# untitled.net
KiCad netlist of a schematic drawn in EAGLE
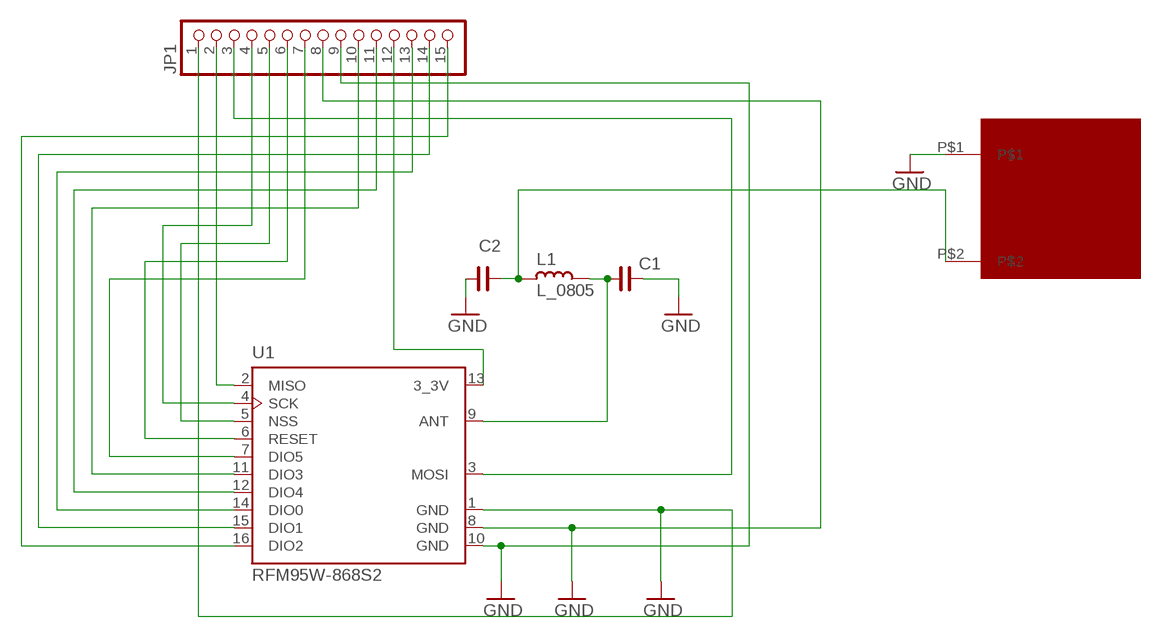
[diagram p0: schematic, sheet 1]

(export (version "E")
  (design (tool "Eeschema 10.0.6"))
  (components
    (comp (ref "C1")
      (value "C_0805")
      (footprint "eagle-import:C0805")
      (libsource (lib "eagle-import") (part "C_0805"))
    )
    (comp (ref "C2")
      (value "C_0805")
      (footprint "eagle-import:C0805")
      (libsource (lib "eagle-import") (part "C_0805"))
    )
    (comp (ref "JP1")
      (value "PINHD-1X15")
      (footprint "eagle-import:1X15")
      (libsource (lib "eagle-import") (part "PINHD-1X15"))
    )
    (comp (ref "L1")
      (value "L_0805")
      (footprint "eagle-import:L0805")
      (libsource (lib "eagle-import") (part "L_0805"))
    )
    (comp (ref "U$1")
      (value "868")
      (footprint "eagle-import:868")
      (libsource (lib "eagle-import") (part "868"))
    )
    (comp (ref "U1")
      (value "RFM95W-868S2")
      (footprint "eagle-import:XCVR_RFM95W-868S2")
      (fields (field (name "MF") "RF"))
      (libsource (lib "eagle-import") (part "RFM95W-868S2"))
    )
  )
  (nets
    (net (code "1") (name "GND") (class "Default")
      (node (ref "C1") (pin "2") (pinfunction "2_2") (pintype "passive"))
      (node (ref "C2") (pin "1") (pinfunction "1_1") (pintype "passive"))
      (node (ref "JP1") (pin "1") (pinfunction "1_1") (pintype "passive"))
      (node (ref "JP1") (pin "8") (pinfunction "8_8") (pintype "passive"))
      (node (ref "JP1") (pin "9") (pinfunction "9_9") (pintype "passive"))
      (node (ref "U$1") (pin "P$1") (pinfunction "P$1_P$1") (pintype "bidirectional"))
      (node (ref "U1") (pin "1") (pinfunction "GND_1") (pintype "power_in"))
      (node (ref "U1") (pin "10") (pinfunction "GND_10") (pintype "power_in"))
      (node (ref "U1") (pin "8") (pinfunction "GND_8") (pintype "power_in"))
    )
    (net (code "2") (name "Net-(C2-Pad2)") (class "Default")
      (node (ref "C2") (pin "2") (pinfunction "2_2") (pintype "passive"))
      (node (ref "L1") (pin "2") (pinfunction "2_2") (pintype "passive"))
      (node (ref "U$1") (pin "P$2") (pinfunction "P$2_P$2") (pintype "bidirectional"))
    )
    (net (code "3") (name "Net-(U1-3_3V)") (class "Default")
      (node (ref "JP1") (pin "12") (pinfunction "12_12") (pintype "passive"))
      (node (ref "U1") (pin "13") (pinfunction "3_3V_13") (pintype "power_in"))
    )
    (net (code "4") (name "Net-(U1-ANT)") (class "Default")
      (node (ref "C1") (pin "1") (pinfunction "1_1") (pintype "passive"))
      (node (ref "L1") (pin "1") (pinfunction "1_1") (pintype "passive"))
      (node (ref "U1") (pin "9") (pinfunction "ANT_9") (pintype "passive"))
    )
    (net (code "5") (name "Net-(U1-DIO0)") (class "Default")
      (node (ref "JP1") (pin "13") (pinfunction "13_13") (pintype "passive"))
      (node (ref "U1") (pin "14") (pinfunction "DIO0_14") (pintype "bidirectional"))
    )
    (net (code "6") (name "Net-(U1-DIO1)") (class "Default")
      (node (ref "JP1") (pin "14") (pinfunction "14_14") (pintype "passive"))
      (node (ref "U1") (pin "15") (pinfunction "DIO1_15") (pintype "bidirectional"))
    )
    (net (code "7") (name "Net-(U1-DIO2)") (class "Default")
      (node (ref "JP1") (pin "15") (pinfunction "15_15") (pintype "passive"))
      (node (ref "U1") (pin "16") (pinfunction "DIO2_16") (pintype "bidirectional"))
    )
    (net (code "8") (name "Net-(U1-DIO3)") (class "Default")
      (node (ref "JP1") (pin "10") (pinfunction "10_10") (pintype "passive"))
      (node (ref "U1") (pin "11") (pinfunction "DIO3_11") (pintype "bidirectional"))
    )
    (net (code "9") (name "Net-(U1-DIO4)") (class "Default")
      (node (ref "JP1") (pin "11") (pinfunction "11_11") (pintype "passive"))
      (node (ref "U1") (pin "12") (pinfunction "DIO4_12") (pintype "bidirectional"))
    )
    (net (code "10") (name "Net-(U1-DIO5)") (class "Default")
      (node (ref "JP1") (pin "7") (pinfunction "7_7") (pintype "passive"))
      (node (ref "U1") (pin "7") (pinfunction "DIO5_7") (pintype "bidirectional"))
    )
    (net (code "11") (name "Net-(U1-MISO)") (class "Default")
      (node (ref "JP1") (pin "2") (pinfunction "2_2") (pintype "passive"))
      (node (ref "U1") (pin "2") (pinfunction "MISO_2") (pintype "input"))
    )
    (net (code "12") (name "Net-(U1-MOSI)") (class "Default")
      (node (ref "JP1") (pin "3") (pinfunction "3_3") (pintype "passive"))
      (node (ref "U1") (pin "3") (pinfunction "MOSI_3") (pintype "output"))
    )
    (net (code "13") (name "Net-(U1-NSS)") (class "Default")
      (node (ref "JP1") (pin "5") (pinfunction "5_5") (pintype "passive"))
      (node (ref "U1") (pin "5") (pinfunction "NSS_5") (pintype "input"))
    )
    (net (code "14") (name "Net-(U1-RESET)") (class "Default")
      (node (ref "JP1") (pin "6") (pinfunction "6_6") (pintype "passive"))
      (node (ref "U1") (pin "6") (pinfunction "RESET_6") (pintype "bidirectional"))
    )
    (net (code "15") (name "Net-(U1-SCK)") (class "Default")
      (node (ref "JP1") (pin "4") (pinfunction "4_4") (pintype "passive"))
      (node (ref "U1") (pin "4") (pinfunction "SCK_4") (pintype "input"))
    )
  )
)
